# LORA.net
KiCad netlist of a schematic drawn in Altium Designer
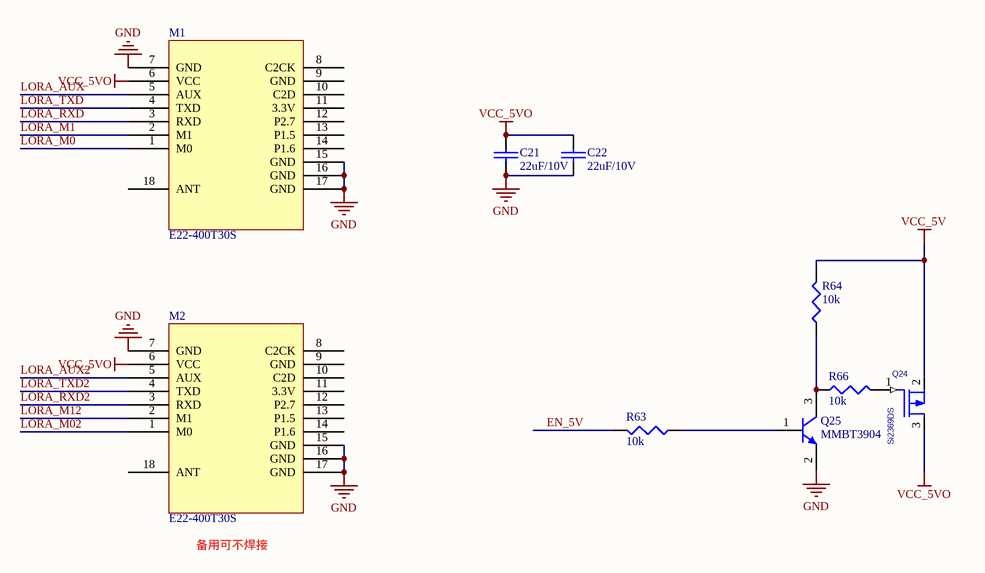
[diagram p0: LORA.SchDoc]

(export (version "E")
  (design (tool "Eeschema 10.0.6"))
  (components
    (comp (ref "C21")
      (value "22uF/10V")
      (footprint "1206C")
      (description "Capacitor")
      (libsource (lib "ZWLIntegrated_Library") (part "CAP"))
    )
    (comp (ref "C22")
      (value "22uF/10V")
      (footprint "1206C")
      (description "Capacitor")
      (libsource (lib "ZWLIntegrated_Library") (part "CAP"))
    )
    (comp (ref "M1")
      (value "E22-400T30S")
      (footprint "E22-400T30S")
      (libsource (lib "stm32") (part "E22-400T30S"))
    )
    (comp (ref "M2")
      (value "E22-400T30S")
      (footprint "E22-400T30S")
      (libsource (lib "stm32") (part "E22-400T30S"))
    )
    (comp (ref "Q24") (value "Si2369DS") (footprint "SOT23") (libsource (lib "*") (part "MOSFET P_1")))
    (comp (ref "Q25") (value "MMBT3904") (footprint "SOT23-3") (libsource (lib "Schlib1") (part "NPN")))
    (comp (ref "R63")
      (value "10k")
      (footprint "0603R")
      (libsource (lib "ZWLIntegrated_Library") (part "RES1"))
    )
    (comp (ref "R64")
      (value "10k")
      (footprint "0603R")
      (libsource (lib "ZWLIntegrated_Library") (part "RES1"))
    )
    (comp (ref "R66")
      (value "10k")
      (footprint "0603R")
      (libsource (lib "ZWLIntegrated_Library") (part "RES1"))
    )
  )
  (nets
    (net (code "1") (name "/EN_5V") (class "Default")
      (node (ref "R63") (pin "2") (pinfunction "2_2") (pintype "passive"))
    )
    (net (code "2") (name "/LORA_AUX") (class "Default")
      (node (ref "M1") (pin "5") (pinfunction "AUX_5") (pintype "passive"))
    )
    (net (code "3") (name "/LORA_AUX2") (class "Default")
      (node (ref "M2") (pin "5") (pinfunction "AUX_5") (pintype "passive"))
    )
    (net (code "4") (name "/LORA_M0") (class "Default")
      (node (ref "M1") (pin "1") (pinfunction "M0_1") (pintype "passive"))
    )
    (net (code "5") (name "/LORA_M1") (class "Default")
      (node (ref "M1") (pin "2") (pinfunction "M1_2") (pintype "passive"))
    )
    (net (code "6") (name "/LORA_M02") (class "Default")
      (node (ref "M2") (pin "1") (pinfunction "M0_1") (pintype "passive"))
    )
    (net (code "7") (name "/LORA_M12") (class "Default")
      (node (ref "M2") (pin "2") (pinfunction "M1_2") (pintype "passive"))
    )
    (net (code "8") (name "/LORA_RXD") (class "Default")
      (node (ref "M1") (pin "3") (pinfunction "RXD_3") (pintype "passive"))
    )
    (net (code "9") (name "/LORA_RXD2") (class "Default")
      (node (ref "M2") (pin "3") (pinfunction "RXD_3") (pintype "passive"))
    )
    (net (code "10") (name "/LORA_TXD") (class "Default")
      (node (ref "M1") (pin "4") (pinfunction "TXD_4") (pintype "passive"))
    )
    (net (code "11") (name "/LORA_TXD2") (class "Default")
      (node (ref "M2") (pin "4") (pinfunction "TXD_4") (pintype "passive"))
    )
    (net (code "12") (name "GND") (class "Default")
      (node (ref "C21") (pin "2") (pinfunction "2_2") (pintype "passive"))
      (node (ref "C22") (pin "2") (pinfunction "2_2") (pintype "passive"))
      (node (ref "M1") (pin "15") (pinfunction "GND_15") (pintype "passive"))
      (node (ref "M1") (pin "16") (pinfunction "GND_16") (pintype "passive"))
      (node (ref "M1") (pin "17") (pinfunction "GND_17") (pintype "passive"))
      (node (ref "M1") (pin "7") (pinfunction "GND_7") (pintype "passive"))
      (node (ref "M2") (pin "15") (pinfunction "GND_15") (pintype "passive"))
      (node (ref "M2") (pin "16") (pinfunction "GND_16") (pintype "passive"))
      (node (ref "M2") (pin "17") (pinfunction "GND_17") (pintype "passive"))
      (node (ref "M2") (pin "7") (pinfunction "GND_7") (pintype "passive"))
      (node (ref "Q25") (pin "2") (pinfunction "E_2") (pintype "passive"))
    )
    (net (code "13") (name "Net-(Q24-GATE)") (class "Default")
      (node (ref "Q24") (pin "1") (pinfunction "GATE_1") (pintype "input"))
      (node (ref "R66") (pin "2") (pinfunction "2_2") (pintype "passive"))
    )
    (net (code "14") (name "Net-(Q25-B)") (class "Default")
      (node (ref "Q25") (pin "1") (pinfunction "B_1") (pintype "passive"))
      (node (ref "R63") (pin "1") (pinfunction "1_1") (pintype "passive"))
    )
    (net (code "15") (name "Net-(Q25-C)") (class "Default")
      (node (ref "Q25") (pin "3") (pinfunction "C_3") (pintype "passive"))
      (node (ref "R64") (pin "1") (pinfunction "1_1") (pintype "passive"))
      (node (ref "R66") (pin "1") (pinfunction "1_1") (pintype "passive"))
    )
    (net (code "16") (name "VCC_5V") (class "Default")
      (node (ref "Q24") (pin "2") (pinfunction "DRAIN_2") (pintype "passive"))
      (node (ref "R64") (pin "2") (pinfunction "2_2") (pintype "passive"))
    )
    (net (code "17") (name "VCC_5VO") (class "Default")
      (node (ref "C21") (pin "1") (pinfunction "1_1") (pintype "passive"))
      (node (ref "C22") (pin "1") (pinfunction "1_1") (pintype "passive"))
      (node (ref "M1") (pin "6") (pinfunction "VCC_6") (pintype "passive"))
      (node (ref "M2") (pin "6") (pinfunction "VCC_6") (pintype "passive"))
      (node (ref "Q24") (pin "3") (pinfunction "SOURCE_3") (pintype "passive"))
    )
    (net (code "18") (name "unconnected-(M1-3.3V-Pad11)") (class "Default")
      (node (ref "M1") (pin "11") (pinfunction "3.3V_11") (pintype "passive"))
    )
    (net (code "19") (name "unconnected-(M1-ANT-Pad18)") (class "Default")
      (node (ref "M1") (pin "18") (pinfunction "ANT_18") (pintype "passive"))
    )
    (net (code "20") (name "unconnected-(M1-C2CK-Pad8)") (class "Default")
      (node (ref "M1") (pin "8") (pinfunction "C2CK_8") (pintype "passive"))
    )
    (net (code "21") (name "unconnected-(M1-C2D-Pad10)") (class "Default")
      (node (ref "M1") (pin "10") (pinfunction "C2D_10") (pintype "passive"))
    )
    (net (code "22") (name "unconnected-(M1-GND-Pad9)") (class "Default")
      (node (ref "M1") (pin "9") (pinfunction "GND_9") (pintype "passive"))
    )
    (net (code "23") (name "unconnected-(M1-P1.5-Pad13)") (class "Default")
      (node (ref "M1") (pin "13") (pinfunction "P1.5_13") (pintype "passive"))
    )
    (net (code "24") (name "unconnected-(M1-P1.6-Pad14)") (class "Default")
      (node (ref "M1") (pin "14") (pinfunction "P1.6_14") (pintype "passive"))
    )
    (net (code "25") (name "unconnected-(M1-P2.7-Pad12)") (class "Default")
      (node (ref "M1") (pin "12") (pinfunction "P2.7_12") (pintype "passive"))
    )
    (net (code "26") (name "unconnected-(M2-3.3V-Pad11)") (class "Default")
      (node (ref "M2") (pin "11") (pinfunction "3.3V_11") (pintype "passive"))
    )
    (net (code "27") (name "unconnected-(M2-ANT-Pad18)") (class "Default")
      (node (ref "M2") (pin "18") (pinfunction "ANT_18") (pintype "passive"))
    )
    (net (code "28") (name "unconnected-(M2-C2CK-Pad8)") (class "Default")
      (node (ref "M2") (pin "8") (pinfunction "C2CK_8") (pintype "passive"))
    )
    (net (code "29") (name "unconnected-(M2-C2D-Pad10)") (class "Default")
      (node (ref "M2") (pin "10") (pinfunction "C2D_10") (pintype "passive"))
    )
    (net (code "30") (name "unconnected-(M2-GND-Pad9)") (class "Default")
      (node (ref "M2") (pin "9") (pinfunction "GND_9") (pintype "passive"))
    )
    (net (code "31") (name "unconnected-(M2-P1.5-Pad13)") (class "Default")
      (node (ref "M2") (pin "13") (pinfunction "P1.5_13") (pintype "passive"))
    )
    (net (code "32") (name "unconnected-(M2-P1.6-Pad14)") (class "Default")
      (node (ref "M2") (pin "14") (pinfunction "P1.6_14") (pintype "passive"))
    )
    (net (code "33") (name "unconnected-(M2-P2.7-Pad12)") (class "Default")
      (node (ref "M2") (pin "12") (pinfunction "P2.7_12") (pintype "passive"))
    )
  )
)
